# pH_to_I2C.net
KiCad netlist of a schematic drawn in EAGLE
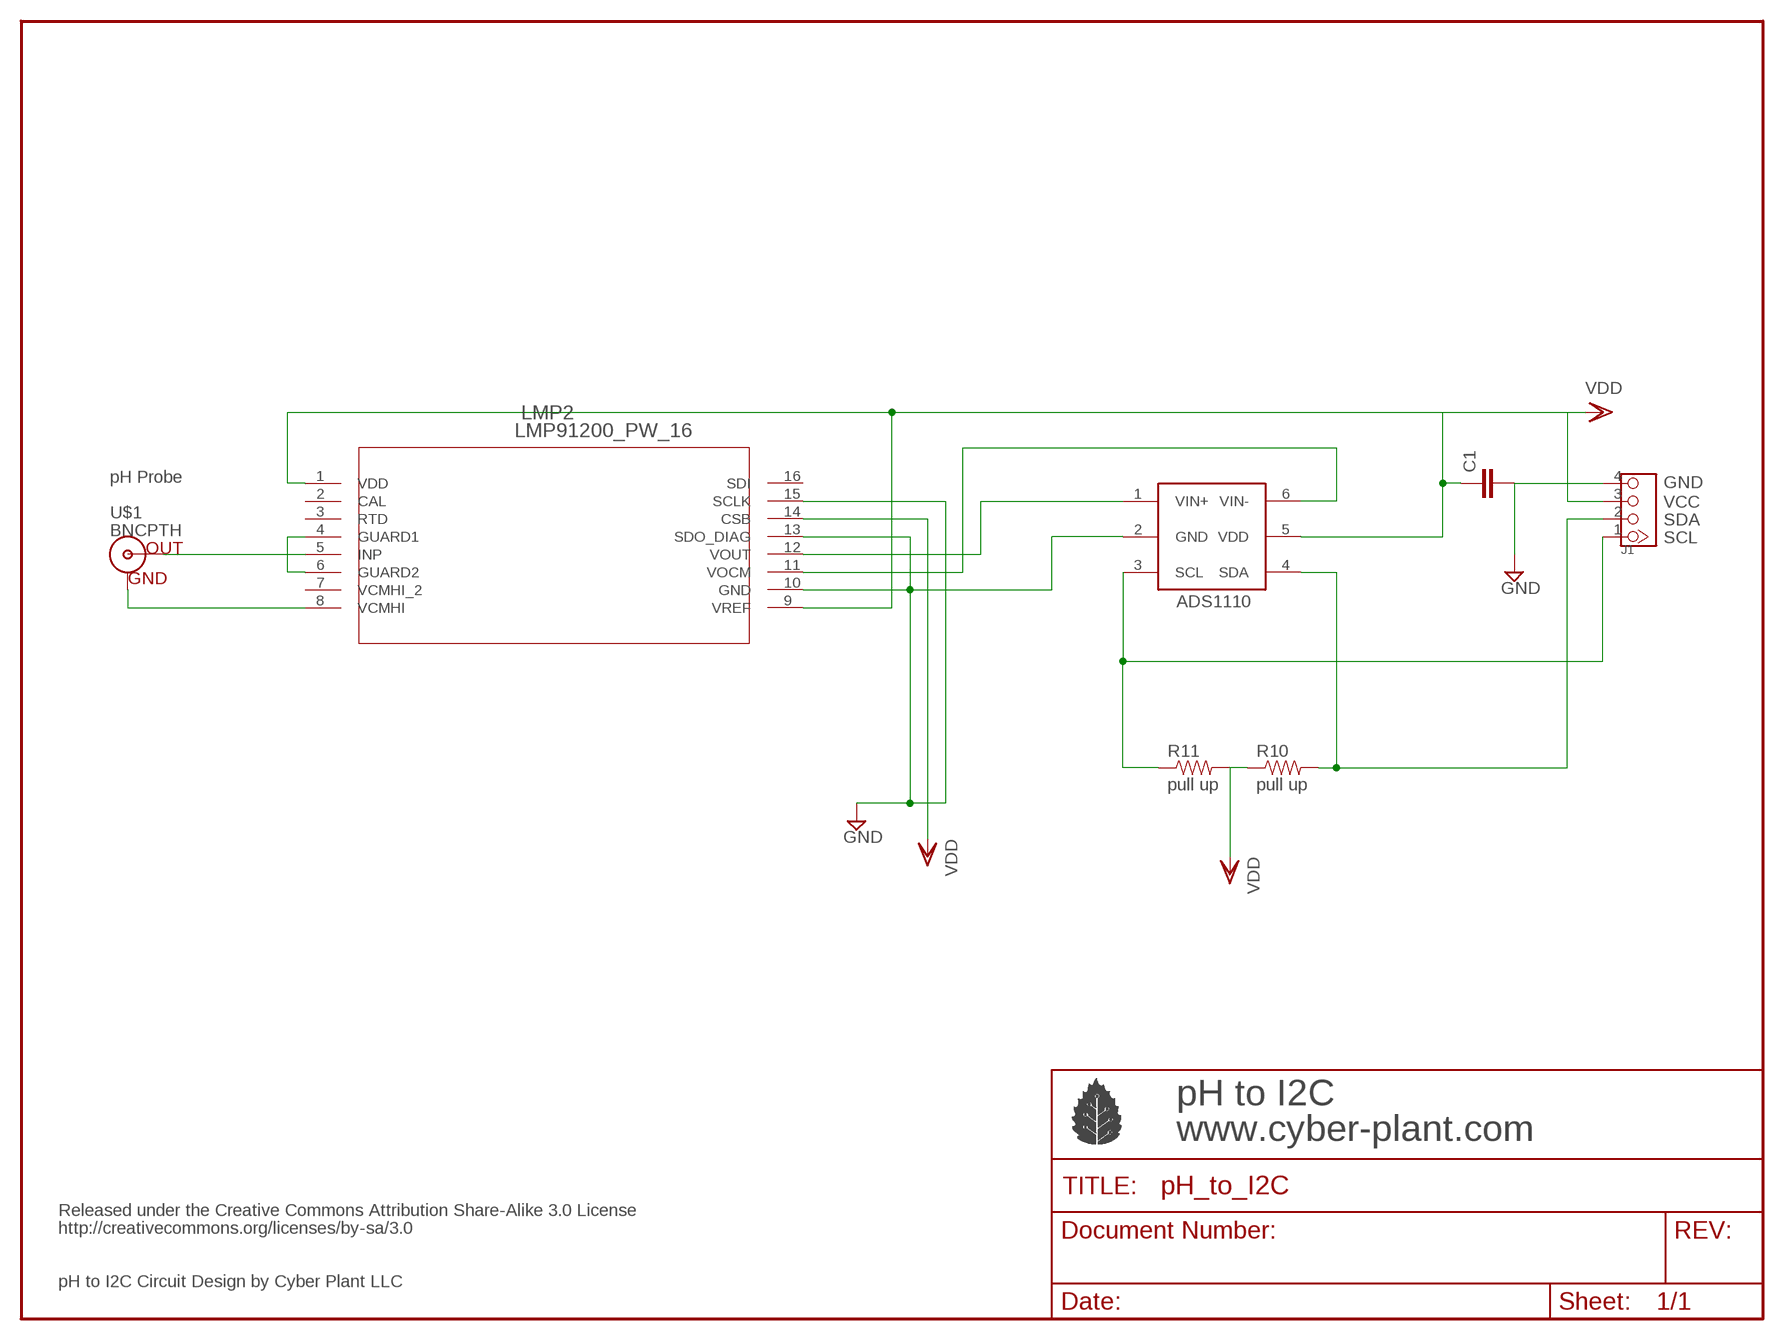
[diagram p0: schematic, sheet 1]

(export (version "E")
  (design (tool "Eeschema 10.0.6"))
  (components
    (comp (ref "C1")
      (value "CAP1206")
      (footprint "eagle-import:1206")
      (libsource (lib "eagle-import") (part "CAP1206"))
    )
    (comp (ref "IC1")
      (value "ADS1110")
      (footprint "eagle-import:SOT-23-6")
      (libsource (lib "eagle-import") (part "ADS1110"))
    )
    (comp (ref "J1")
      (value "TWIG-4P-2.090D")
      (footprint "eagle-import:4P-2.0-90D")
      (libsource (lib "eagle-import") (part "TWIG-4P-2.090D"))
    )
    (comp (ref "LMP2")
      (value "LMP91200_PW_16")
      (footprint "eagle-import:MTC16")
      (fields
        (field (name "MANUFACTURER") "Texas Instruments")
        (field (name "MANUFACTURER_PART_NUMBER") "lmp91200_pw_16")
      )
      (libsource (lib "eagle-import") (part "LMP91200_PW_16"))
    )
    (comp (ref "R10")
      (value "pull up")
      (footprint "eagle-import:AXIAL-0.4")
      (libsource (lib "eagle-import") (part "RESISTORPTH-1/4W"))
    )
    (comp (ref "R11")
      (value "pull up")
      (footprint "eagle-import:AXIAL-0.4")
      (libsource (lib "eagle-import") (part "RESISTORPTH-1/4W"))
    )
    (comp (ref "U$1")
      (value "BNCPTH")
      (footprint "eagle-import:BNC")
      (libsource (lib "eagle-import") (part "BNCPTH"))
    )
  )
  (nets
    (net (code "1") (name "GND") (class "Default")
      (node (ref "C1") (pin "2") (pinfunction "2_2") (pintype "passive"))
      (node (ref "IC1") (pin "2") (pinfunction "GND_2") (pintype "bidirectional"))
      (node (ref "J1") (pin "4") (pinfunction "4_4") (pintype "bidirectional"))
      (node (ref "LMP2") (pin "10") (pinfunction "GND_10") (pintype "power_in"))
      (node (ref "LMP2") (pin "13") (pinfunction "SDO_DIAG_13") (pintype "bidirectional"))
      (node (ref "LMP2") (pin "15") (pinfunction "SCLK_15") (pintype "passive"))
    )
    (net (code "2") (name "Net-(IC1-SCL)") (class "Default")
      (node (ref "IC1") (pin "3") (pinfunction "SCL_3") (pintype "bidirectional"))
      (node (ref "J1") (pin "1") (pinfunction "1_1") (pintype "bidirectional"))
      (node (ref "R11") (pin "P$1") (pinfunction "1_P$1") (pintype "passive"))
    )
    (net (code "3") (name "Net-(IC1-SDA)") (class "Default")
      (node (ref "IC1") (pin "4") (pinfunction "SDA_4") (pintype "bidirectional"))
      (node (ref "J1") (pin "2") (pinfunction "2_2") (pintype "bidirectional"))
      (node (ref "R10") (pin "P$2") (pinfunction "2_P$2") (pintype "passive"))
    )
    (net (code "4") (name "Net-(IC1-VIN+)") (class "Default")
      (node (ref "IC1") (pin "1") (pinfunction "VIN+_1") (pintype "bidirectional"))
      (node (ref "LMP2") (pin "12") (pinfunction "VOUT_12") (pintype "output"))
    )
    (net (code "5") (name "Net-(IC1-VIN-)") (class "Default")
      (node (ref "IC1") (pin "6") (pinfunction "VIN-_6") (pintype "bidirectional"))
      (node (ref "LMP2") (pin "11") (pinfunction "VOCM_11") (pintype "output"))
    )
    (net (code "6") (name "Net-(LMP2-GUARD1)") (class "Default")
      (node (ref "LMP2") (pin "4") (pinfunction "GUARD1_4") (pintype "passive"))
      (node (ref "LMP2") (pin "6") (pinfunction "GUARD2_6") (pintype "passive"))
    )
    (net (code "7") (name "Net-(LMP2-INP)") (class "Default")
      (node (ref "LMP2") (pin "5") (pinfunction "INP_5") (pintype "input"))
      (node (ref "U$1") (pin "S") (pinfunction "OUT_S") (pintype "bidirectional"))
    )
    (net (code "8") (name "Net-(LMP2-VCMHI)") (class "Default")
      (node (ref "LMP2") (pin "8") (pinfunction "VCMHI_8") (pintype "output"))
      (node (ref "U$1") (pin "GND") (pinfunction "GND_GND") (pintype "bidirectional"))
    )
    (net (code "9") (name "VDD") (class "Default")
      (node (ref "C1") (pin "1") (pinfunction "1_1") (pintype "passive"))
      (node (ref "IC1") (pin "5") (pinfunction "VDD_5") (pintype "bidirectional"))
      (node (ref "J1") (pin "3") (pinfunction "3_3") (pintype "bidirectional"))
      (node (ref "LMP2") (pin "1") (pinfunction "VDD_1") (pintype "power_in"))
      (node (ref "LMP2") (pin "14") (pinfunction "CSB_14") (pintype "passive"))
      (node (ref "LMP2") (pin "9") (pinfunction "VREF_9") (pintype "input"))
      (node (ref "R10") (pin "P$1") (pinfunction "1_P$1") (pintype "passive"))
      (node (ref "R11") (pin "P$2") (pinfunction "2_P$2") (pintype "passive"))
    )
    (net (code "10") (name "unconnected-(LMP2-CAL-Pad2)") (class "Default")
      (node (ref "LMP2") (pin "2") (pinfunction "CAL_2") (pintype "passive"))
    )
    (net (code "11") (name "unconnected-(LMP2-RTD-Pad3)") (class "Default")
      (node (ref "LMP2") (pin "3") (pinfunction "RTD_3") (pintype "bidirectional"))
    )
    (net (code "12") (name "unconnected-(LMP2-SDI-Pad16)") (class "Default")
      (node (ref "LMP2") (pin "16") (pinfunction "SDI_16") (pintype "passive"))
    )
    (net (code "13") (name "unconnected-(LMP2-VCMHI_2-Pad7)") (class "Default")
      (node (ref "LMP2") (pin "7") (pinfunction "VCMHI_2_7") (pintype "output"))
    )
  )
)
